# Schemat.net
KiCad netlist of a schematic drawn in EAGLE
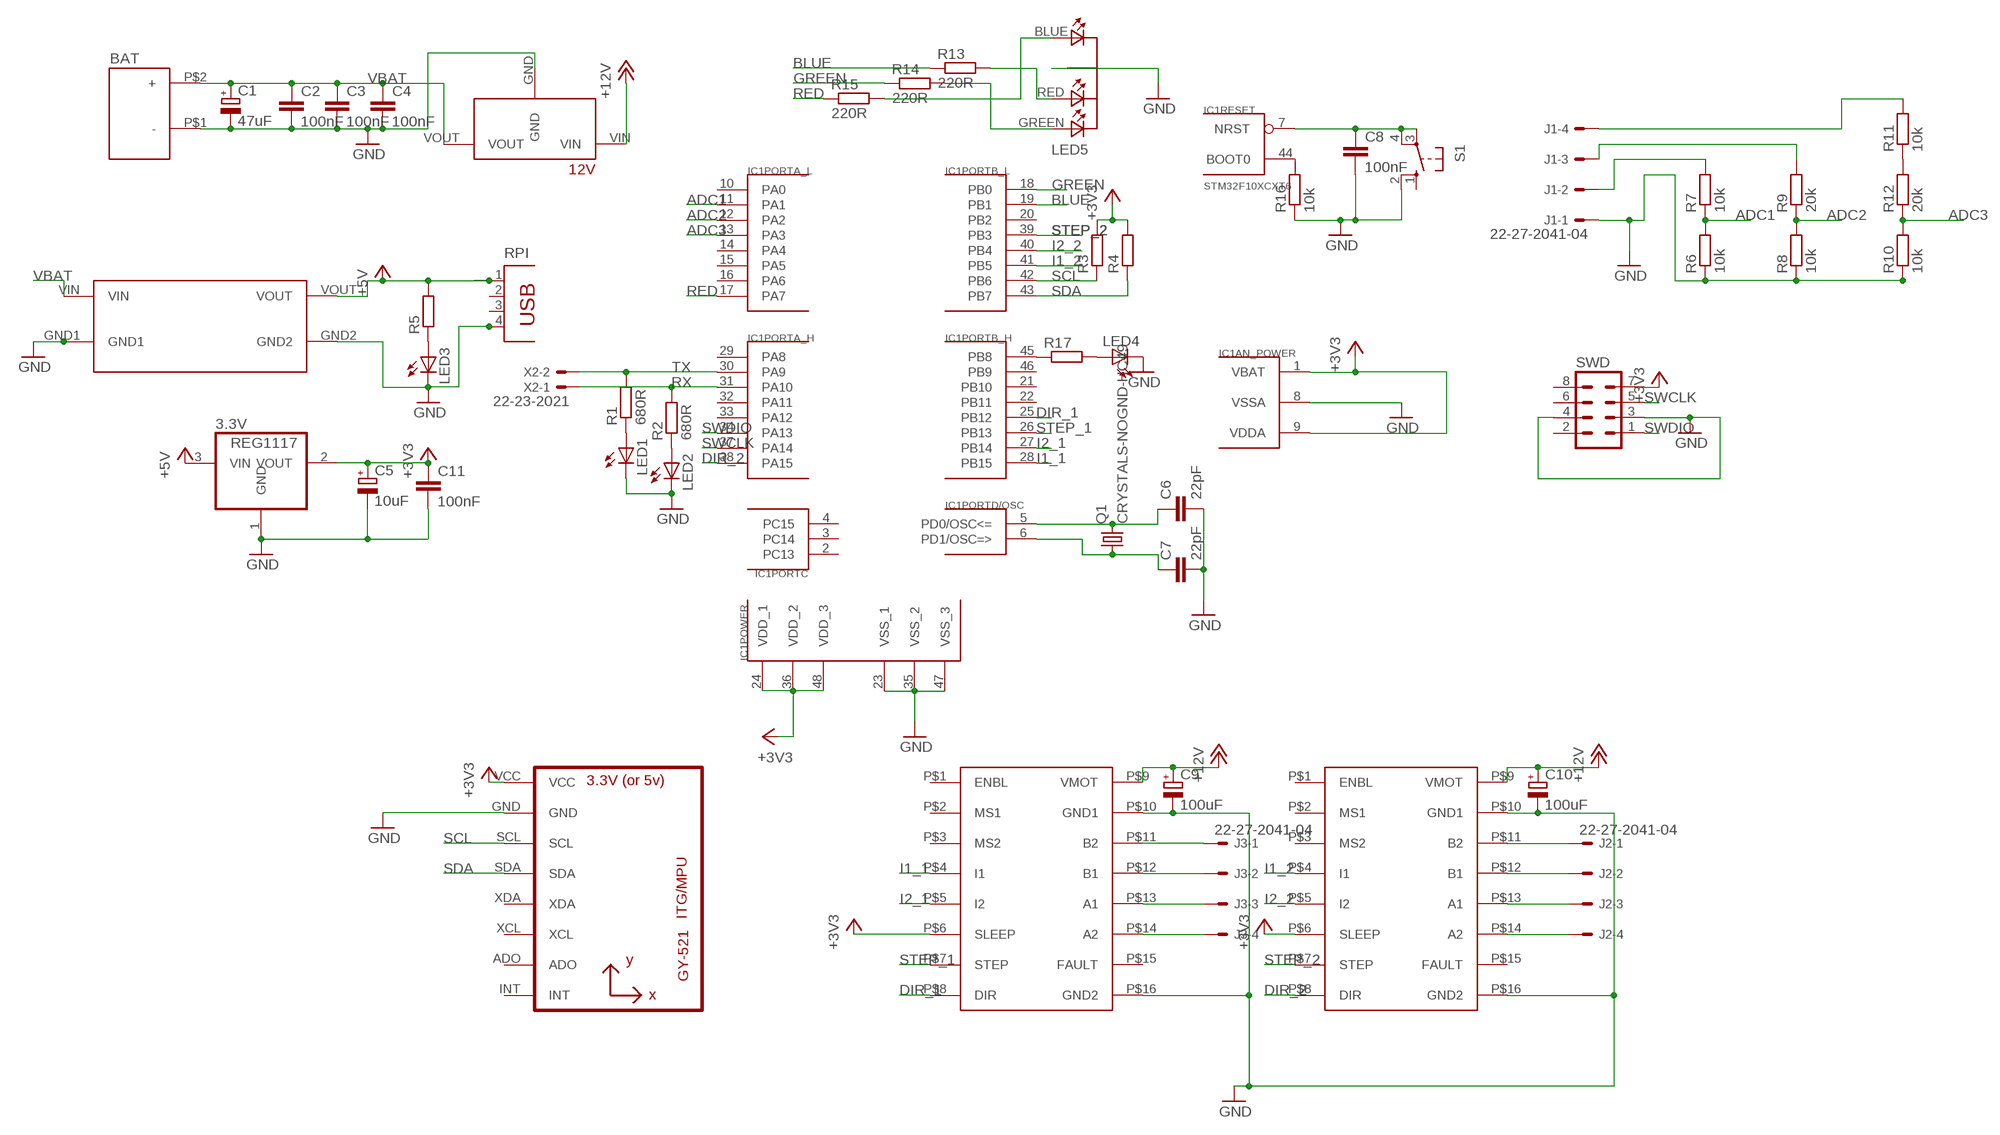
[diagram p0: schematic, sheet 1]

(export (version "E")
  (design (tool "Eeschema 10.0.6"))
  (components
    (comp (ref "3.3V")
      (value "REG1117")
      (footprint "eagle-import:SOT223")
      (libsource (lib "eagle-import") (part "REG1117"))
    )
    (comp (ref "12V")
      (value "12V_VOLTAGE_REGULATOR")
      (footprint "eagle-import:9V_VOLTAGE_REGULATOR")
      (libsource (lib "eagle-import") (part "9V_VOLTAGE_REGULATOR"))
    )
    (comp (ref "BAT")
      (value "DEANS")
      (footprint "eagle-import:DEAN")
      (libsource (lib "eagle-import") (part "DEANS"))
    )
    (comp (ref "C1")
      (value "47uF")
      (footprint "eagle-import:E2-5")
      (libsource (lib "eagle-import") (part "CPOL-EUE2-5"))
    )
    (comp (ref "C2")
      (value "100nF")
      (footprint "eagle-import:C0603K")
      (libsource (lib "eagle-import") (part "C-EUC0603K"))
    )
    (comp (ref "C3")
      (value "100nF")
      (footprint "eagle-import:C0603K")
      (libsource (lib "eagle-import") (part "C-EUC0603K"))
    )
    (comp (ref "C4")
      (value "100nF")
      (footprint "eagle-import:C0603K")
      (libsource (lib "eagle-import") (part "C-EUC0603K"))
    )
    (comp (ref "C5")
      (value "10uF")
      (footprint "eagle-import:E2-5")
      (libsource (lib "eagle-import") (part "CPOL-EUE2-5"))
    )
    (comp (ref "C6")
      (value "22pF")
      (footprint "eagle-import:C0603K")
      (libsource (lib "eagle-import") (part "C-EUC0603K"))
    )
    (comp (ref "C7")
      (value "22pF")
      (footprint "eagle-import:C0603K")
      (libsource (lib "eagle-import") (part "C-EUC0603K"))
    )
    (comp (ref "C8")
      (value "100nF")
      (footprint "eagle-import:C050-030X075")
      (libsource (lib "eagle-import") (part "C-EU050-030X075"))
    )
    (comp (ref "C9")
      (value "100uF")
      (footprint "eagle-import:E2,5-7")
      (libsource (lib "eagle-import") (part "CPOL-EUE2.5-7"))
    )
    (comp (ref "C10")
      (value "100uF")
      (footprint "eagle-import:E2,5-7")
      (libsource (lib "eagle-import") (part "CPOL-EUE2.5-7"))
    )
    (comp (ref "C11")
      (value "100nF")
      (footprint "eagle-import:C0603")
      (libsource (lib "eagle-import") (part "C-EUC0603"))
    )
    (comp (ref "DRV1")
      (value "POLOLU-MP6500")
      (footprint "eagle-import:STEPPER-CARRIER")
      (libsource (lib "eagle-import") (part "POLOLU-MP6500"))
    )
    (comp (ref "DRV2")
      (value "POLOLU-MP6500")
      (footprint "eagle-import:STEPPER-CARRIER")
      (libsource (lib "eagle-import") (part "POLOLU-MP6500"))
    )
    (comp (ref "IC1")
      (value "STM32F10XCXT6")
      (footprint "eagle-import:TQFP48")
      (libsource (lib "eagle-import") (part "STM32F10XCXT6"))
    )
    (comp (ref "J1")
      (value "22-27-2041-04")
      (footprint "eagle-import:6410-04")
      (fields (field (name "MF") "MOLEX"))
      (libsource (lib "eagle-import") (part "22-?-0427-2041"))
    )
    (comp (ref "J2")
      (value "22-27-2041-04")
      (footprint "eagle-import:6410-04")
      (fields (field (name "MF") "MOLEX"))
      (libsource (lib "eagle-import") (part "22-?-0427-2041"))
    )
    (comp (ref "J3")
      (value "22-27-2041-04")
      (footprint "eagle-import:6410-04")
      (fields (field (name "MF") "MOLEX"))
      (libsource (lib "eagle-import") (part "22-?-0427-2041"))
    )
    (comp (ref "LED1")
      (value "LEDSML0603")
      (footprint "eagle-import:SML0603")
      (libsource (lib "eagle-import") (part "LEDSML0603"))
    )
    (comp (ref "LED2")
      (value "LEDSML0603")
      (footprint "eagle-import:SML0603")
      (libsource (lib "eagle-import") (part "LEDSML0603"))
    )
    (comp (ref "LED3")
      (value "LED5MM")
      (footprint "eagle-import:LED5MM")
      (libsource (lib "eagle-import") (part "LED5MM"))
    )
    (comp (ref "LED4")
      (value "LED5MM")
      (footprint "eagle-import:LED5MM")
      (libsource (lib "eagle-import") (part "LED5MM"))
    )
    (comp (ref "LED5")
      (value "LED-DIP-3")
      (footprint "eagle-import:DIP-4")
      (libsource (lib "eagle-import") (part "LED-DIP-3"))
    )
    (comp (ref "Q1")
      (value "CRYSTALS-NOGND-HC49")
      (footprint "eagle-import:HC49")
      (libsource (lib "eagle-import") (part "CRYSTALS-NOGND-HC49"))
    )
    (comp (ref "R1")
      (value "680R")
      (footprint "eagle-import:R0805")
      (libsource (lib "eagle-import") (part "R-EU_R0805"))
    )
    (comp (ref "R2")
      (value "680R")
      (footprint "eagle-import:R0805")
      (libsource (lib "eagle-import") (part "R-EU_R0805"))
    )
    (comp (ref "R3")
      (value "R-EU_R0805")
      (footprint "eagle-import:R0805")
      (libsource (lib "eagle-import") (part "R-EU_R0805"))
    )
    (comp (ref "R4")
      (value "R-EU_R0805")
      (footprint "eagle-import:R0805")
      (libsource (lib "eagle-import") (part "R-EU_R0805"))
    )
    (comp (ref "R5")
      (value "R-EU_R0805")
      (footprint "eagle-import:R0805")
      (libsource (lib "eagle-import") (part "R-EU_R0805"))
    )
    (comp (ref "R6")
      (value "10k")
      (footprint "eagle-import:R0805")
      (libsource (lib "eagle-import") (part "R-EU_R0805"))
    )
    (comp (ref "R7")
      (value "10k")
      (footprint "eagle-import:R0805")
      (libsource (lib "eagle-import") (part "R-EU_R0805"))
    )
    (comp (ref "R8")
      (value "10k")
      (footprint "eagle-import:R0805")
      (libsource (lib "eagle-import") (part "R-EU_R0805"))
    )
    (comp (ref "R9")
      (value "20k")
      (footprint "eagle-import:R0805")
      (libsource (lib "eagle-import") (part "R-EU_R0805"))
    )
    (comp (ref "R10")
      (value "10k")
      (footprint "eagle-import:R0805")
      (libsource (lib "eagle-import") (part "R-EU_R0805"))
    )
    (comp (ref "R11")
      (value "10k")
      (footprint "eagle-import:R0805")
      (libsource (lib "eagle-import") (part "R-EU_R0805"))
    )
    (comp (ref "R12")
      (value "20k")
      (footprint "eagle-import:R0805")
      (libsource (lib "eagle-import") (part "R-EU_R0805"))
    )
    (comp (ref "R13")
      (value "220R")
      (footprint "eagle-import:R0805")
      (libsource (lib "eagle-import") (part "R-EU_R0805"))
    )
    (comp (ref "R14")
      (value "220R")
      (footprint "eagle-import:R0805")
      (libsource (lib "eagle-import") (part "R-EU_R0805"))
    )
    (comp (ref "R15")
      (value "220R")
      (footprint "eagle-import:R0805")
      (libsource (lib "eagle-import") (part "R-EU_R0805"))
    )
    (comp (ref "R16")
      (value "10k")
      (footprint "eagle-import:R0805")
      (libsource (lib "eagle-import") (part "R-EU_R0805"))
    )
    (comp (ref "R17")
      (value "R-EU_R0805")
      (footprint "eagle-import:R0805")
      (libsource (lib "eagle-import") (part "R-EU_R0805"))
    )
    (comp (ref "RPI")
      (value "PN87520")
      (footprint "eagle-import:PN87520")
      (libsource (lib "eagle-import") (part "PN87520"))
    )
    (comp (ref "S1")
      (value "10-XX")
      (footprint "eagle-import:B3F-10XX")
      (fields (field (name "MPN") "B3F-1000"))
      (libsource (lib "eagle-import") (part "10-XX"))
    )
    (comp (ref "SWD")
      (value "MA04-2")
      (footprint "eagle-import:MA04-2")
      (libsource (lib "eagle-import") (part "MA04-2"))
    )
    (comp (ref "U$1")
      (value "DC-DC")
      (footprint "eagle-import:DC-DC")
      (libsource (lib "eagle-import") (part "DC-DC"))
    )
    (comp (ref "U1")
      (value "GY-521MPU6050")
      (footprint "eagle-import:GY-521")
      (libsource (lib "eagle-import") (part "GY-521MPU6050"))
    )
    (comp (ref "X2")
      (value "22-23-2021")
      (footprint "eagle-import:22-23-2021")
      (fields (field (name "MF") "MOLEX"))
      (libsource (lib "eagle-import") (part "22-23-2021"))
    )
  )
  (nets
    (net (code "1") (name "+3V3") (class "Default")
      (node (ref "3.3V") (pin "2") (pinfunction "VOUT_2") (pintype "output"))
      (node (ref "C11") (pin "1") (pinfunction "1_1") (pintype "passive"))
      (node (ref "C5") (pin "+") (pinfunction "+_+") (pintype "passive"))
      (node (ref "DRV1") (pin "P$6") (pinfunction "SLEEP_P$6") (pintype "bidirectional"))
      (node (ref "DRV2") (pin "P$6") (pinfunction "SLEEP_P$6") (pintype "bidirectional"))
      (node (ref "IC1") (pin "1") (pinfunction "VBAT_1") (pintype "power_in"))
      (node (ref "IC1") (pin "24") (pinfunction "VDD_1_24") (pintype "power_in"))
      (node (ref "IC1") (pin "36") (pinfunction "VDD_2_36") (pintype "power_in"))
      (node (ref "IC1") (pin "48") (pinfunction "VDD_3_48") (pintype "power_in"))
      (node (ref "IC1") (pin "9") (pinfunction "VDDA_9") (pintype "power_in"))
      (node (ref "R3") (pin "2") (pinfunction "2_2") (pintype "passive"))
      (node (ref "R4") (pin "2") (pinfunction "2_2") (pintype "passive"))
      (node (ref "SWD") (pin "7") (pinfunction "7_7") (pintype "passive"))
      (node (ref "U1") (pin "VCC") (pinfunction "VCC_VCC") (pintype "bidirectional"))
    )
    (net (code "2") (name "+5V") (class "Default")
      (node (ref "3.3V") (pin "3") (pinfunction "VIN_3") (pintype "input"))
      (node (ref "R5") (pin "2") (pinfunction "2_2") (pintype "passive"))
      (node (ref "RPI") (pin "1") (pinfunction "1_1") (pintype "passive"))
      (node (ref "U$1") (pin "VOUT") (pinfunction "VOUT_VOUT") (pintype "bidirectional"))
    )
    (net (code "3") (name "+12V") (class "Default")
      (node (ref "12V") (pin "VIN") (pinfunction "VIN_VIN") (pintype "bidirectional"))
      (node (ref "C10") (pin "+") (pinfunction "+_+") (pintype "passive"))
      (node (ref "C9") (pin "+") (pinfunction "+_+") (pintype "passive"))
      (node (ref "DRV1") (pin "P$9") (pinfunction "VMOT_P$9") (pintype "bidirectional"))
      (node (ref "DRV2") (pin "P$9") (pinfunction "VMOT_P$9") (pintype "bidirectional"))
    )
    (net (code "4") (name "/ADC1") (class "Default")
      (node (ref "IC1") (pin "11") (pinfunction "PA1_11") (pintype "bidirectional"))
      (node (ref "R6") (pin "2") (pinfunction "2_2") (pintype "passive"))
      (node (ref "R7") (pin "1") (pinfunction "1_1") (pintype "passive"))
    )
    (net (code "5") (name "/ADC2") (class "Default")
      (node (ref "IC1") (pin "12") (pinfunction "PA2_12") (pintype "bidirectional"))
      (node (ref "R8") (pin "2") (pinfunction "2_2") (pintype "passive"))
      (node (ref "R9") (pin "1") (pinfunction "1_1") (pintype "passive"))
    )
    (net (code "6") (name "/ADC3") (class "Default")
      (node (ref "IC1") (pin "13") (pinfunction "PA3_13") (pintype "bidirectional"))
      (node (ref "R10") (pin "2") (pinfunction "2_2") (pintype "passive"))
      (node (ref "R12") (pin "1") (pinfunction "1_1") (pintype "passive"))
    )
    (net (code "7") (name "/BLUE") (class "Default")
      (node (ref "IC1") (pin "19") (pinfunction "PB1_19") (pintype "bidirectional"))
      (node (ref "R13") (pin "1") (pinfunction "1_1") (pintype "passive"))
    )
    (net (code "8") (name "/DIR_1") (class "Default")
      (node (ref "DRV1") (pin "P$8") (pinfunction "DIR_P$8") (pintype "bidirectional"))
      (node (ref "IC1") (pin "25") (pinfunction "PB12_25") (pintype "bidirectional"))
    )
    (net (code "9") (name "/DIR_2") (class "Default")
      (node (ref "DRV2") (pin "P$8") (pinfunction "DIR_P$8") (pintype "bidirectional"))
      (node (ref "IC1") (pin "38") (pinfunction "PA15_38") (pintype "bidirectional"))
    )
    (net (code "10") (name "/GREEN") (class "Default")
      (node (ref "IC1") (pin "18") (pinfunction "PB0_18") (pintype "bidirectional"))
      (node (ref "R14") (pin "1") (pinfunction "1_1") (pintype "passive"))
    )
    (net (code "11") (name "/I1_1") (class "Default")
      (node (ref "DRV1") (pin "P$4") (pinfunction "I1_P$4") (pintype "bidirectional"))
      (node (ref "IC1") (pin "28") (pinfunction "PB15_28") (pintype "bidirectional"))
    )
    (net (code "12") (name "/I1_2") (class "Default")
      (node (ref "DRV2") (pin "P$4") (pinfunction "I1_P$4") (pintype "bidirectional"))
      (node (ref "IC1") (pin "41") (pinfunction "PB5_41") (pintype "bidirectional"))
    )
    (net (code "13") (name "/I2_1") (class "Default")
      (node (ref "DRV1") (pin "P$5") (pinfunction "I2_P$5") (pintype "bidirectional"))
      (node (ref "IC1") (pin "27") (pinfunction "PB14_27") (pintype "bidirectional"))
    )
    (net (code "14") (name "/I2_2") (class "Default")
      (node (ref "DRV2") (pin "P$5") (pinfunction "I2_P$5") (pintype "bidirectional"))
      (node (ref "IC1") (pin "40") (pinfunction "PB4_40") (pintype "bidirectional"))
    )
    (net (code "15") (name "/RED") (class "Default")
      (node (ref "IC1") (pin "17") (pinfunction "PA7_17") (pintype "bidirectional"))
      (node (ref "R15") (pin "1") (pinfunction "1_1") (pintype "passive"))
    )
    (net (code "16") (name "/RX") (class "Default")
      (node (ref "IC1") (pin "31") (pinfunction "PA10_31") (pintype "bidirectional"))
      (node (ref "R2") (pin "2") (pinfunction "2_2") (pintype "passive"))
      (node (ref "X2") (pin "1") (pinfunction "S_1") (pintype "passive"))
    )
    (net (code "17") (name "/SCL") (class "Default")
      (node (ref "IC1") (pin "42") (pinfunction "PB6_42") (pintype "bidirectional"))
      (node (ref "R3") (pin "1") (pinfunction "1_1") (pintype "passive"))
      (node (ref "U1") (pin "SCL") (pinfunction "SCL_SCL") (pintype "bidirectional"))
    )
    (net (code "18") (name "/SDA") (class "Default")
      (node (ref "IC1") (pin "43") (pinfunction "PB7_43") (pintype "bidirectional"))
      (node (ref "R4") (pin "1") (pinfunction "1_1") (pintype "passive"))
      (node (ref "U1") (pin "SDA") (pinfunction "SDA_SDA") (pintype "bidirectional"))
    )
    (net (code "19") (name "/STEP_1") (class "Default")
      (node (ref "DRV1") (pin "P$7") (pinfunction "STEP_P$7") (pintype "bidirectional"))
      (node (ref "IC1") (pin "26") (pinfunction "PB13_26") (pintype "bidirectional"))
    )
    (net (code "20") (name "/STEP_2") (class "Default")
      (node (ref "DRV2") (pin "P$7") (pinfunction "STEP_P$7") (pintype "bidirectional"))
      (node (ref "IC1") (pin "39") (pinfunction "PB3_39") (pintype "bidirectional"))
    )
    (net (code "21") (name "/SWCLK") (class "Default")
      (node (ref "IC1") (pin "37") (pinfunction "PA14_37") (pintype "bidirectional"))
      (node (ref "SWD") (pin "5") (pinfunction "5_5") (pintype "passive"))
    )
    (net (code "22") (name "/SWDIO") (class "Default")
      (node (ref "IC1") (pin "34") (pinfunction "PA13_34") (pintype "bidirectional"))
      (node (ref "SWD") (pin "1") (pinfunction "1_1") (pintype "passive"))
    )
    (net (code "23") (name "/TX") (class "Default")
      (node (ref "IC1") (pin "30") (pinfunction "PA9_30") (pintype "bidirectional"))
      (node (ref "R1") (pin "2") (pinfunction "2_2") (pintype "passive"))
      (node (ref "X2") (pin "2") (pinfunction "S_2") (pintype "passive"))
    )
    (net (code "24") (name "/VBAT") (class "Default")
      (node (ref "12V") (pin "VOUT") (pinfunction "VOUT_VOUT") (pintype "bidirectional"))
      (node (ref "BAT") (pin "P$2") (pinfunction "+_P$2") (pintype "bidirectional"))
      (node (ref "C1") (pin "+") (pinfunction "+_+") (pintype "passive"))
      (node (ref "C2") (pin "1") (pinfunction "1_1") (pintype "passive"))
      (node (ref "C3") (pin "1") (pinfunction "1_1") (pintype "passive"))
      (node (ref "C4") (pin "1") (pinfunction "1_1") (pintype "passive"))
      (node (ref "U$1") (pin "VIN") (pinfunction "VIN_VIN") (pintype "bidirectional"))
    )
    (net (code "25") (name "GND") (class "Default")
      (node (ref "12V") (pin "GND") (pinfunction "GND_GND") (pintype "bidirectional"))
      (node (ref "3.3V") (pin "1") (pinfunction "GND_1") (pintype "power_in"))
      (node (ref "BAT") (pin "P$1") (pinfunction "-_P$1") (pintype "bidirectional"))
      (node (ref "C1") (pin "-") (pinfunction "-_-") (pintype "passive"))
      (node (ref "C10") (pin "-") (pinfunction "-_-") (pintype "passive"))
      (node (ref "C11") (pin "2") (pinfunction "2_2") (pintype "passive"))
      (node (ref "C2") (pin "2") (pinfunction "2_2") (pintype "passive"))
      (node (ref "C3") (pin "2") (pinfunction "2_2") (pintype "passive"))
      (node (ref "C4") (pin "2") (pinfunction "2_2") (pintype "passive"))
      (node (ref "C5") (pin "-") (pinfunction "-_-") (pintype "passive"))
      (node (ref "C6") (pin "2") (pinfunction "2_2") (pintype "passive"))
      (node (ref "C7") (pin "2") (pinfunction "2_2") (pintype "passive"))
      (node (ref "C8") (pin "2") (pinfunction "2_2") (pintype "passive"))
      (node (ref "C9") (pin "-") (pinfunction "-_-") (pintype "passive"))
      (node (ref "DRV1") (pin "P$10") (pinfunction "GND1_P$10") (pintype "bidirectional"))
      (node (ref "DRV1") (pin "P$16") (pinfunction "GND2_P$16") (pintype "bidirectional"))
      (node (ref "DRV2") (pin "P$10") (pinfunction "GND1_P$10") (pintype "bidirectional"))
      (node (ref "DRV2") (pin "P$16") (pinfunction "GND2_P$16") (pintype "bidirectional"))
      (node (ref "IC1") (pin "23") (pinfunction "VSS_1_23") (pintype "power_in"))
      (node (ref "IC1") (pin "35") (pinfunction "VSS_2_35") (pintype "power_in"))
      (node (ref "IC1") (pin "47") (pinfunction "VSS_3_47") (pintype "power_in"))
      (node (ref "IC1") (pin "8") (pinfunction "VSSA_8") (pintype "power_in"))
      (node (ref "J1") (pin "1") (pinfunction "S_1") (pintype "passive"))
      (node (ref "LED1") (pin "C") (pinfunction "C_C") (pintype "passive"))
      (node (ref "LED2") (pin "C") (pinfunction "C_C") (pintype "passive"))
      (node (ref "LED3") (pin "K") (pinfunction "C_K") (pintype "passive"))
      (node (ref "LED4") (pin "K") (pinfunction "C_K") (pintype "passive"))
      (node (ref "LED5") (pin "COMMON_CATHODE") (pinfunction "COM-CATHODE_COMMON_CATHODE") (pintype "passive"))
      (node (ref "R10") (pin "1") (pinfunction "1_1") (pintype "passive"))
      (node (ref "R16") (pin "1") (pinfunction "1_1") (pintype "passive"))
      (node (ref "R6") (pin "1") (pinfunction "1_1") (pintype "passive"))
      (node (ref "R8") (pin "1") (pinfunction "1_1") (pintype "passive"))
      (node (ref "RPI") (pin "4") (pinfunction "4_4") (pintype "passive"))
      (node (ref "S1") (pin "2") (pinfunction "S1_2") (pintype "passive"))
      (node (ref "SWD") (pin "3") (pinfunction "3_3") (pintype "passive"))
      (node (ref "SWD") (pin "4") (pinfunction "4_4") (pintype "passive"))
      (node (ref "U$1") (pin "GND1") (pinfunction "GND1_GND1") (pintype "bidirectional"))
      (node (ref "U$1") (pin "GND2") (pinfunction "GND2_GND2") (pintype "bidirectional"))
      (node (ref "U1") (pin "GND") (pinfunction "GND_GND") (pintype "bidirectional"))
    )
    (net (code "26") (name "Net-(DRV1-A1)") (class "Default")
      (node (ref "DRV1") (pin "P$13") (pinfunction "A1_P$13") (pintype "bidirectional"))
      (node (ref "J3") (pin "3") (pinfunction "S_3") (pintype "passive"))
    )
    (net (code "27") (name "Net-(DRV1-A2)") (class "Default")
      (node (ref "DRV1") (pin "P$14") (pinfunction "A2_P$14") (pintype "bidirectional"))
      (node (ref "J3") (pin "4") (pinfunction "S_4") (pintype "passive"))
    )
    (net (code "28") (name "Net-(DRV1-B1)") (class "Default")
      (node (ref "DRV1") (pin "P$12") (pinfunction "B1_P$12") (pintype "bidirectional"))
      (node (ref "J3") (pin "2") (pinfunction "S_2") (pintype "passive"))
    )
    (net (code "29") (name "Net-(DRV1-B2)") (class "Default")
      (node (ref "DRV1") (pin "P$11") (pinfunction "B2_P$11") (pintype "bidirectional"))
      (node (ref "J3") (pin "1") (pinfunction "S_1") (pintype "passive"))
    )
    (net (code "30") (name "Net-(DRV2-A1)") (class "Default")
      (node (ref "DRV2") (pin "P$13") (pinfunction "A1_P$13") (pintype "bidirectional"))
      (node (ref "J2") (pin "3") (pinfunction "S_3") (pintype "passive"))
    )
    (net (code "31") (name "Net-(DRV2-A2)") (class "Default")
      (node (ref "DRV2") (pin "P$14") (pinfunction "A2_P$14") (pintype "bidirectional"))
      (node (ref "J2") (pin "4") (pinfunction "S_4") (pintype "passive"))
    )
    (net (code "32") (name "Net-(DRV2-B1)") (class "Default")
      (node (ref "DRV2") (pin "P$12") (pinfunction "B1_P$12") (pintype "bidirectional"))
      (node (ref "J2") (pin "2") (pinfunction "S_2") (pintype "passive"))
    )
    (net (code "33") (name "Net-(DRV2-B2)") (class "Default")
      (node (ref "DRV2") (pin "P$11") (pinfunction "B2_P$11") (pintype "bidirectional"))
      (node (ref "J2") (pin "1") (pinfunction "S_1") (pintype "passive"))
    )
    (net (code "34") (name "Net-(IC1D-PB8)") (class "Default")
      (node (ref "IC1") (pin "45") (pinfunction "PB8_45") (pintype "bidirectional"))
      (node (ref "R17") (pin "1") (pinfunction "1_1") (pintype "passive"))
    )
    (net (code "35") (name "Net-(IC1G-PD0{slash}OSC<=)") (class "Default")
      (node (ref "C6") (pin "1") (pinfunction "1_1") (pintype "passive"))
      (node (ref "IC1") (pin "5") (pinfunction "PD0/OSC<=_5") (pintype "bidirectional"))
      (node (ref "Q1") (pin "2") (pinfunction "2_2") (pintype "passive"))
    )
    (net (code "36") (name "Net-(IC1G-PD1{slash}OSC=>)") (class "Default")
      (node (ref "C7") (pin "1") (pinfunction "1_1") (pintype "passive"))
      (node (ref "IC1") (pin "6") (pinfunction "PD1/OSC=>_6") (pintype "bidirectional"))
      (node (ref "Q1") (pin "1") (pinfunction "1_1") (pintype "passive"))
    )
    (net (code "37") (name "Net-(IC1I-BOOT0)") (class "Default")
      (node (ref "IC1") (pin "44") (pinfunction "BOOT0_44") (pintype "input"))
      (node (ref "R16") (pin "2") (pinfunction "2_2") (pintype "passive"))
    )
    (net (code "38") (name "Net-(IC1I-NRST)") (class "Default")
      (node (ref "C8") (pin "1") (pinfunction "1_1") (pintype "passive"))
      (node (ref "IC1") (pin "7") (pinfunction "NRST_7") (pintype "input"))
      (node (ref "S1") (pin "3") (pinfunction "P_3") (pintype "passive"))
      (node (ref "S1") (pin "4") (pinfunction "P1_4") (pintype "passive"))
    )
    (net (code "39") (name "Net-(J1B-S)") (class "Default")
      (node (ref "J1") (pin "2") (pinfunction "S_2") (pintype "passive"))
      (node (ref "R7") (pin "2") (pinfunction "2_2") (pintype "passive"))
    )
    (net (code "40") (name "Net-(J1C-S)") (class "Default")
      (node (ref "J1") (pin "3") (pinfunction "S_3") (pintype "passive"))
      (node (ref "R9") (pin "2") (pinfunction "2_2") (pintype "passive"))
    )
    (net (code "41") (name "Net-(J1D-S)") (class "Default")
      (node (ref "J1") (pin "4") (pinfunction "S_4") (pintype "passive"))
      (node (ref "R11") (pin "2") (pinfunction "2_2") (pintype "passive"))
    )
    (net (code "42") (name "Net-(LED1-PadA)") (class "Default")
      (node (ref "LED1") (pin "A") (pinfunction "A_A") (pintype "passive"))
      (node (ref "R1") (pin "1") (pinfunction "1_1") (pintype "passive"))
    )
    (net (code "43") (name "Net-(LED2-PadA)") (class "Default")
      (node (ref "LED2") (pin "A") (pinfunction "A_A") (pintype "passive"))
      (node (ref "R2") (pin "1") (pinfunction "1_1") (pintype "passive"))
    )
    (net (code "44") (name "Net-(LED3-PadA)") (class "Default")
      (node (ref "LED3") (pin "A") (pinfunction "A_A") (pintype "passive"))
      (node (ref "R5") (pin "1") (pinfunction "1_1") (pintype "passive"))
    )
    (net (code "45") (name "Net-(LED4-PadA)") (class "Default")
      (node (ref "LED4") (pin "A") (pinfunction "A_A") (pintype "passive"))
      (node (ref "R17") (pin "2") (pinfunction "2_2") (pintype "passive"))
    )
    (net (code "46") (name "Net-(LED5-PadBLUE)") (class "Default")
      (node (ref "LED5") (pin "BLUE") (pinfunction "BLUE_BLUE") (pintype "passive"))
      (node (ref "R15") (pin "2") (pinfunction "2_2") (pintype "passive"))
    )
    (net (code "47") (name "Net-(LED5-PadGREEN)") (class "Default")
      (node (ref "LED5") (pin "GREEN") (pinfunction "GREEN_GREEN") (pintype "passive"))
      (node (ref "R14") (pin "2") (pinfunction "2_2") (pintype "passive"))
    )
    (net (code "48") (name "Net-(LED5-PadRED)") (class "Default")
      (node (ref "LED5") (pin "RED") (pinfunction "RED_RED") (pintype "passive"))
      (node (ref "R13") (pin "2") (pinfunction "2_2") (pintype "passive"))
    )
    (net (code "49") (name "Net-(R11-Pad1)") (class "Default")
      (node (ref "R11") (pin "1") (pinfunction "1_1") (pintype "passive"))
      (node (ref "R12") (pin "2") (pinfunction "2_2") (pintype "passive"))
    )
    (net (code "50") (name "unconnected-(DRV1-ENBL-PadP$1)") (class "Default")
      (node (ref "DRV1") (pin "P$1") (pinfunction "ENBL_P$1") (pintype "bidirectional"))
    )
    (net (code "51") (name "unconnected-(DRV1-FAULT-PadP$15)") (class "Default")
      (node (ref "DRV1") (pin "P$15") (pinfunction "FAULT_P$15") (pintype "bidirectional"))
    )
    (net (code "52") (name "unconnected-(DRV1-MS1-PadP$2)") (class "Default")
      (node (ref "DRV1") (pin "P$2") (pinfunction "MS1_P$2") (pintype "bidirectional"))
    )
    (net (code "53") (name "unconnected-(DRV1-MS2-PadP$3)") (class "Default")
      (node (ref "DRV1") (pin "P$3") (pinfunction "MS2_P$3") (pintype "bidirectional"))
    )
    (net (code "54") (name "unconnected-(DRV2-ENBL-PadP$1)") (class "Default")
      (node (ref "DRV2") (pin "P$1") (pinfunction "ENBL_P$1") (pintype "bidirectional"))
    )
    (net (code "55") (name "unconnected-(DRV2-FAULT-PadP$15)") (class "Default")
      (node (ref "DRV2") (pin "P$15") (pinfunction "FAULT_P$15") (pintype "bidirectional"))
    )
    (net (code "56") (name "unconnected-(DRV2-MS1-PadP$2)") (class "Default")
      (node (ref "DRV2") (pin "P$2") (pinfunction "MS1_P$2") (pintype "bidirectional"))
    )
    (net (code "57") (name "unconnected-(DRV2-MS2-PadP$3)") (class "Default")
      (node (ref "DRV2") (pin "P$3") (pinfunction "MS2_P$3") (pintype "bidirectional"))
    )
    (net (code "58") (name "unconnected-(IC1B-PA8-Pad29)") (class "Default")
      (node (ref "IC1") (pin "29") (pinfunction "PA8_29") (pintype "bidirectional"))
    )
    (net (code "59") (name "unconnected-(IC1B-PA11-Pad32)") (class "Default")
      (node (ref "IC1") (pin "32") (pinfunction "PA11_32") (pintype "bidirectional"))
    )
    (net (code "60") (name "unconnected-(IC1B-PA12-Pad33)") (class "Default")
      (node (ref "IC1") (pin "33") (pinfunction "PA12_33") (pintype "bidirectional"))
    )
    (net (code "61") (name "unconnected-(IC1C-PA0-Pad10)") (class "Default")
      (node (ref "IC1") (pin "10") (pinfunction "PA0_10") (pintype "bidirectional"))
    )
    (net (code "62") (name "unconnected-(IC1C-PA4-Pad14)") (class "Default")
      (node (ref "IC1") (pin "14") (pinfunction "PA4_14") (pintype "bidirectional"))
    )
    (net (code "63") (name "unconnected-(IC1C-PA5-Pad15)") (class "Default")
      (node (ref "IC1") (pin "15") (pinfunction "PA5_15") (pintype "bidirectional"))
    )
    (net (code "64") (name "unconnected-(IC1C-PA6-Pad16)") (class "Default")
      (node (ref "IC1") (pin "16") (pinfunction "PA6_16") (pintype "bidirectional"))
    )
    (net (code "65") (name "unconnected-(IC1D-PB9-Pad46)") (class "Default")
      (node (ref "IC1") (pin "46") (pinfunction "PB9_46") (pintype "bidirectional"))
    )
    (net (code "66") (name "unconnected-(IC1D-PB10-Pad21)") (class "Default")
      (node (ref "IC1") (pin "21") (pinfunction "PB10_21") (pintype "bidirectional"))
    )
    (net (code "67") (name "unconnected-(IC1D-PB11-Pad22)") (class "Default")
      (node (ref "IC1") (pin "22") (pinfunction "PB11_22") (pintype "bidirectional"))
    )
    (net (code "68") (name "unconnected-(IC1E-PB2-Pad20)") (class "Default")
      (node (ref "IC1") (pin "20") (pinfunction "PB2_20") (pintype "bidirectional"))
    )
    (net (code "69") (name "unconnected-(IC1F-PC13-Pad2)") (class "Default")
      (node (ref "IC1") (pin "2") (pinfunction "PC13_2") (pintype "bidirectional"))
    )
    (net (code "70") (name "unconnected-(IC1F-PC14-Pad3)") (class "Default")
      (node (ref "IC1") (pin "3") (pinfunction "PC14_3") (pintype "bidirectional"))
    )
    (net (code "71") (name "unconnected-(IC1F-PC15-Pad4)") (class "Default")
      (node (ref "IC1") (pin "4") (pinfunction "PC15_4") (pintype "bidirectional"))
    )
    (net (code "72") (name "unconnected-(RPI-Pad2)") (class "Default")
      (node (ref "RPI") (pin "2") (pinfunction "2_2") (pintype "passive"))
    )
    (net (code "73") (name "unconnected-(RPI-Pad3)") (class "Default")
      (node (ref "RPI") (pin "3") (pinfunction "3_3") (pintype "passive"))
    )
    (net (code "74") (name "unconnected-(S1-S-Pad1)") (class "Default")
      (node (ref "S1") (pin "1") (pinfunction "S_1") (pintype "passive"))
    )
    (net (code "75") (name "unconnected-(SWD-Pad2)") (class "Default")
      (node (ref "SWD") (pin "2") (pinfunction "2_2") (pintype "passive"))
    )
    (net (code "76") (name "unconnected-(SWD-Pad6)") (class "Default")
      (node (ref "SWD") (pin "6") (pinfunction "6_6") (pintype "passive"))
    )
    (net (code "77") (name "unconnected-(SWD-Pad8)") (class "Default")
      (node (ref "SWD") (pin "8") (pinfunction "8_8") (pintype "passive"))
    )
    (net (code "78") (name "unconnected-(U1-PadADO)") (class "Default")
      (node (ref "U1") (pin "ADO") (pinfunction "ADO_ADO") (pintype "bidirectional"))
    )
    (net (code "79") (name "unconnected-(U1-PadINT)") (class "Default")
      (node (ref "U1") (pin "INT") (pinfunction "INT_INT") (pintype "bidirectional"))
    )
    (net (code "80") (name "unconnected-(U1-PadXCL)") (class "Default")
      (node (ref "U1") (pin "XCL") (pinfunction "XCL_XCL") (pintype "bidirectional"))
    )
    (net (code "81") (name "unconnected-(U1-PadXDA)") (class "Default")
      (node (ref "U1") (pin "XDA") (pinfunction "XDA_XDA") (pintype "bidirectional"))
    )
  )
)
